# SmartDana.net
KiCad netlist of a schematic drawn in EAGLE
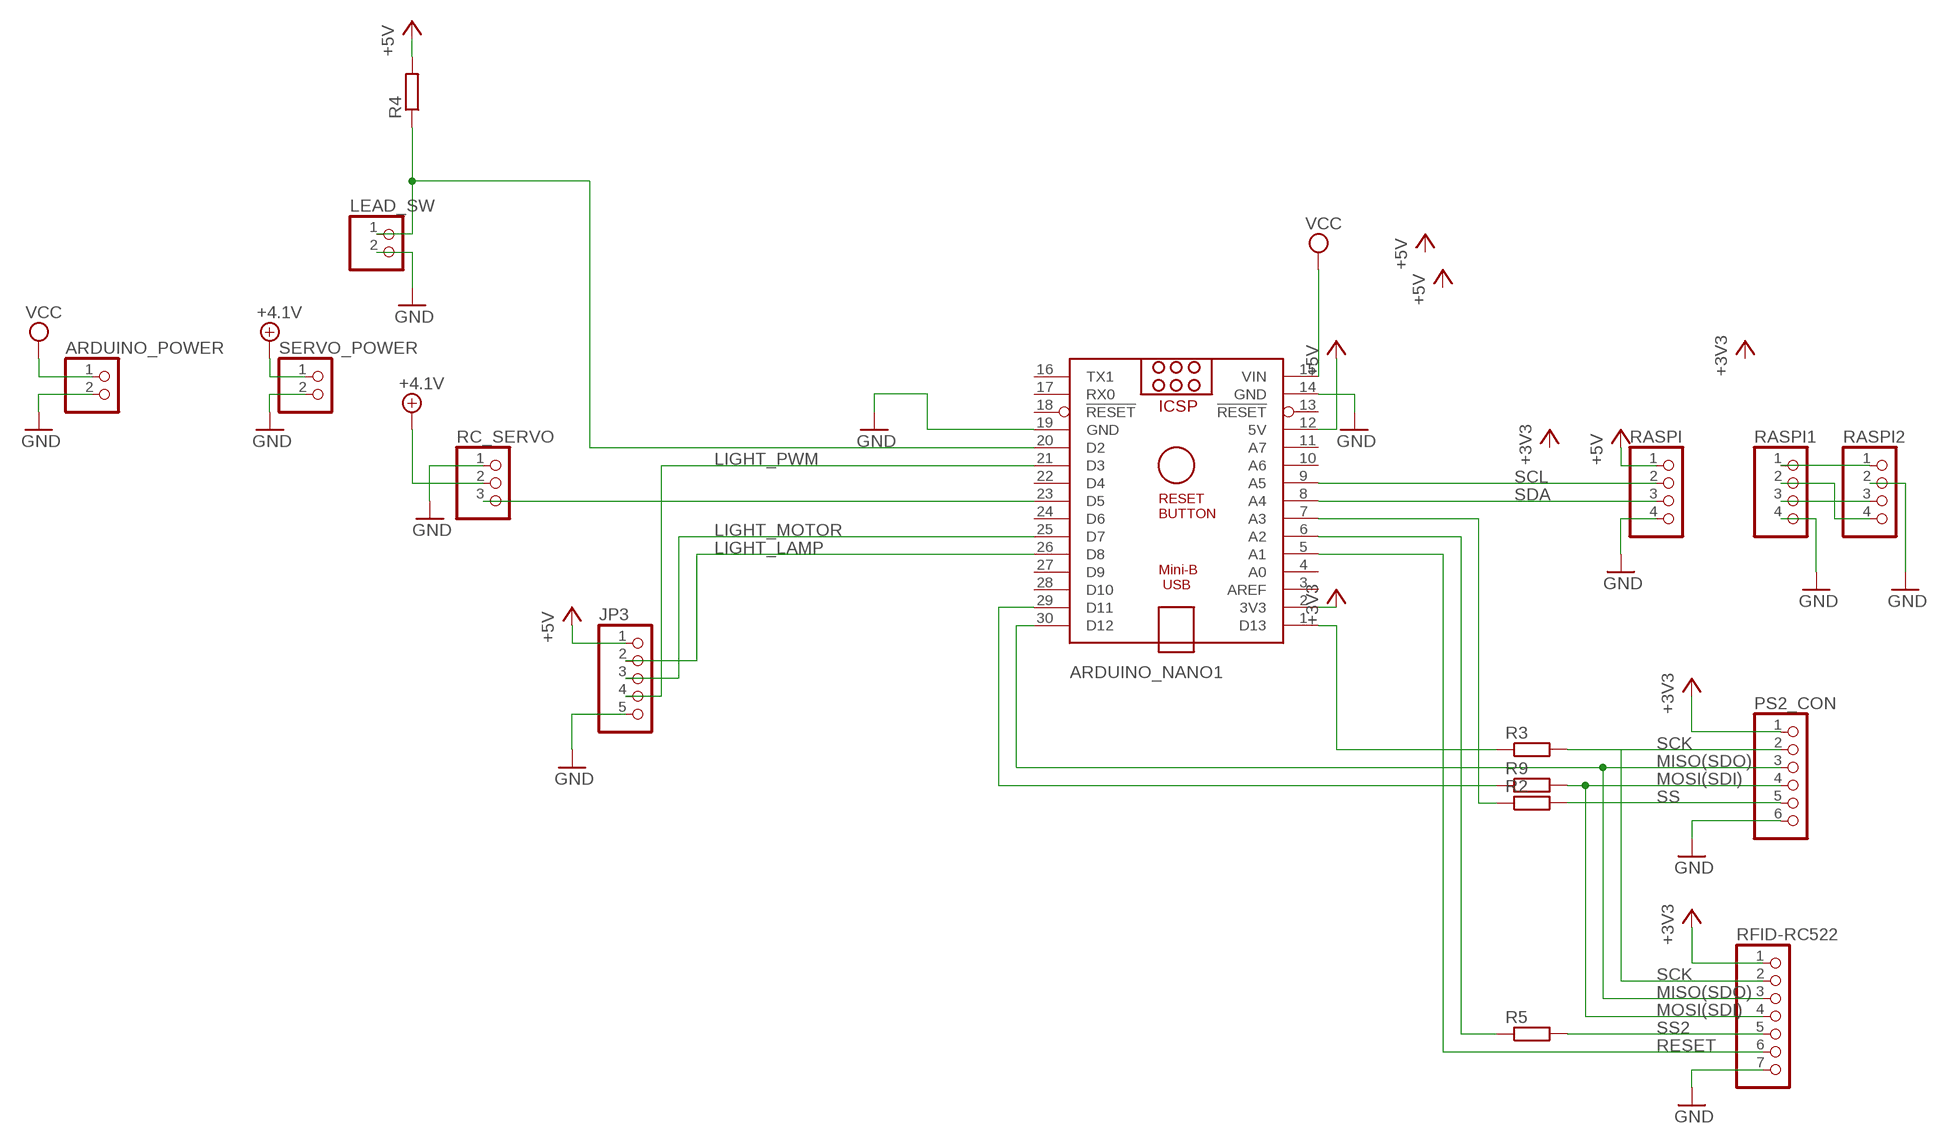
[diagram p0: schematic, sheet 1]

(export (version "E")
  (design (tool "Eeschema 10.0.6"))
  (components
    (comp (ref "ARDUINO_NANO1")
      (value "ARDUINO_NANO")
      (footprint "eagle-import:ARDUINO_NANO")
      (libsource (lib "eagle-import") (part "ARDUINO_NANO"))
    )
    (comp (ref "ARDUINO_POWER")
      (value "PINHD-1X2")
      (footprint "eagle-import:1X02")
      (libsource (lib "eagle-import") (part "PINHD-1X2"))
    )
    (comp (ref "JP3")
      (value "PINHD-1X5")
      (footprint "eagle-import:1X05")
      (libsource (lib "eagle-import") (part "PINHD-1X5"))
    )
    (comp (ref "LEAD_SW")
      (value "PINHD-1X2")
      (footprint "eagle-import:1X02")
      (libsource (lib "eagle-import") (part "PINHD-1X2"))
    )
    (comp (ref "PS2_CON")
      (value "PINHD-1X6")
      (footprint "eagle-import:1X06")
      (libsource (lib "eagle-import") (part "PINHD-1X6"))
    )
    (comp (ref "R2")
      (value "R-EU_0204/7")
      (footprint "eagle-import:0204_7")
      (libsource (lib "eagle-import") (part "R-EU_0204/7"))
    )
    (comp (ref "R3")
      (value "R-EU_0204/7")
      (footprint "eagle-import:0204_7")
      (libsource (lib "eagle-import") (part "R-EU_0204/7"))
    )
    (comp (ref "R4")
      (value "R-EU_0204/7")
      (footprint "eagle-import:0204_7")
      (libsource (lib "eagle-import") (part "R-EU_0204/7"))
    )
    (comp (ref "R5")
      (value "R-EU_0204/7")
      (footprint "eagle-import:0204_7")
      (libsource (lib "eagle-import") (part "R-EU_0204/7"))
    )
    (comp (ref "R9")
      (value "R-EU_0204/7")
      (footprint "eagle-import:0204_7")
      (libsource (lib "eagle-import") (part "R-EU_0204/7"))
    )
    (comp (ref "RASPI")
      (value "PINHD-1X4")
      (footprint "eagle-import:1X04")
      (libsource (lib "eagle-import") (part "PINHD-1X4"))
    )
    (comp (ref "RASPI1")
      (value "PINHD-1X4")
      (footprint "eagle-import:1X04")
      (libsource (lib "eagle-import") (part "PINHD-1X4"))
    )
    (comp (ref "RASPI2")
      (value "PINHD-1X4")
      (footprint "eagle-import:1X04")
      (libsource (lib "eagle-import") (part "PINHD-1X4"))
    )
    (comp (ref "RC_SERVO")
      (value "PINHD-1X3")
      (footprint "eagle-import:1X03")
      (libsource (lib "eagle-import") (part "PINHD-1X3"))
    )
    (comp (ref "RFID-RC522")
      (value "PINHD-1X7")
      (footprint "eagle-import:1X07")
      (libsource (lib "eagle-import") (part "PINHD-1X7"))
    )
    (comp (ref "SERVO_POWER")
      (value "PINHD-1X2")
      (footprint "eagle-import:1X02")
      (libsource (lib "eagle-import") (part "PINHD-1X2"))
    )
  )
  (nets
    (net (code "1") (name "+3V3") (class "Default")
      (node (ref "ARDUINO_NANO1") (pin "2") (pinfunction "3V3_2") (pintype "output"))
      (node (ref "PS2_CON") (pin "1") (pinfunction "1_1") (pintype "passive"))
      (node (ref "RFID-RC522") (pin "1") (pinfunction "1_1") (pintype "passive"))
    )
    (net (code "2") (name "+4.1V") (class "Default")
      (node (ref "RC_SERVO") (pin "2") (pinfunction "2_2") (pintype "passive"))
      (node (ref "SERVO_POWER") (pin "1") (pinfunction "1_1") (pintype "passive"))
    )
    (net (code "3") (name "+5V") (class "Default")
      (node (ref "ARDUINO_NANO1") (pin "12") (pinfunction "5V_12") (pintype "power_in"))
      (node (ref "JP3") (pin "1") (pinfunction "1_1") (pintype "passive"))
      (node (ref "R4") (pin "2") (pinfunction "2_2") (pintype "passive"))
      (node (ref "RASPI") (pin "1") (pinfunction "1_1") (pintype "passive"))
    )
    (net (code "4") (name "/LIGHT_LAMP") (class "Default")
      (node (ref "ARDUINO_NANO1") (pin "26") (pinfunction "D8_26") (pintype "bidirectional"))
      (node (ref "JP3") (pin "2") (pinfunction "2_2") (pintype "passive"))
    )
    (net (code "5") (name "/LIGHT_MOTOR") (class "Default")
      (node (ref "ARDUINO_NANO1") (pin "25") (pinfunction "D7_25") (pintype "bidirectional"))
      (node (ref "JP3") (pin "3") (pinfunction "3_3") (pintype "passive"))
    )
    (net (code "6") (name "/LIGHT_PWM") (class "Default")
      (node (ref "ARDUINO_NANO1") (pin "21") (pinfunction "D3_21") (pintype "bidirectional"))
      (node (ref "JP3") (pin "4") (pinfunction "4_4") (pintype "passive"))
    )
    (net (code "7") (name "/MISO(SDO)") (class "Default")
      (node (ref "ARDUINO_NANO1") (pin "30") (pinfunction "D12_30") (pintype "bidirectional"))
      (node (ref "PS2_CON") (pin "3") (pinfunction "3_3") (pintype "passive"))
      (node (ref "RFID-RC522") (pin "3") (pinfunction "3_3") (pintype "passive"))
    )
    (net (code "8") (name "/MOSI(SDI)") (class "Default")
      (node (ref "PS2_CON") (pin "4") (pinfunction "4_4") (pintype "passive"))
      (node (ref "R9") (pin "2") (pinfunction "2_2") (pintype "passive"))
      (node (ref "RFID-RC522") (pin "4") (pinfunction "4_4") (pintype "passive"))
    )
    (net (code "9") (name "/RESET") (class "Default")
      (node (ref "ARDUINO_NANO1") (pin "5") (pinfunction "A1_5") (pintype "bidirectional"))
      (node (ref "RFID-RC522") (pin "6") (pinfunction "6_6") (pintype "passive"))
    )
    (net (code "10") (name "/SCK") (class "Default")
      (node (ref "PS2_CON") (pin "2") (pinfunction "2_2") (pintype "passive"))
      (node (ref "R3") (pin "2") (pinfunction "2_2") (pintype "passive"))
      (node (ref "RFID-RC522") (pin "2") (pinfunction "2_2") (pintype "passive"))
    )
    (net (code "11") (name "/SCL") (class "Default")
      (node (ref "ARDUINO_NANO1") (pin "9") (pinfunction "A5_9") (pintype "bidirectional"))
      (node (ref "RASPI") (pin "2") (pinfunction "2_2") (pintype "passive"))
    )
    (net (code "12") (name "/SDA") (class "Default")
      (node (ref "ARDUINO_NANO1") (pin "8") (pinfunction "A4_8") (pintype "bidirectional"))
      (node (ref "RASPI") (pin "3") (pinfunction "3_3") (pintype "passive"))
    )
    (net (code "13") (name "/SS") (class "Default")
      (node (ref "PS2_CON") (pin "5") (pinfunction "5_5") (pintype "passive"))
      (node (ref "R2") (pin "2") (pinfunction "2_2") (pintype "passive"))
    )
    (net (code "14") (name "/SS2") (class "Default")
      (node (ref "R5") (pin "2") (pinfunction "2_2") (pintype "passive"))
      (node (ref "RFID-RC522") (pin "5") (pinfunction "5_5") (pintype "passive"))
    )
    (net (code "15") (name "GND") (class "Default")
      (node (ref "ARDUINO_NANO1") (pin "14") (pinfunction "GND_14") (pintype "power_in"))
      (node (ref "ARDUINO_NANO1") (pin "19") (pinfunction "GND_19") (pintype "power_in"))
      (node (ref "ARDUINO_POWER") (pin "2") (pinfunction "2_2") (pintype "passive"))
      (node (ref "JP3") (pin "5") (pinfunction "5_5") (pintype "passive"))
      (node (ref "LEAD_SW") (pin "2") (pinfunction "2_2") (pintype "passive"))
      (node (ref "PS2_CON") (pin "6") (pinfunction "6_6") (pintype "passive"))
      (node (ref "RASPI") (pin "4") (pinfunction "4_4") (pintype "passive"))
      (node (ref "RASPI1") (pin "4") (pinfunction "4_4") (pintype "passive"))
      (node (ref "RASPI2") (pin "2") (pinfunction "2_2") (pintype "passive"))
      (node (ref "RC_SERVO") (pin "1") (pinfunction "1_1") (pintype "passive"))
      (node (ref "RFID-RC522") (pin "7") (pinfunction "7_7") (pintype "passive"))
      (node (ref "SERVO_POWER") (pin "2") (pinfunction "2_2") (pintype "passive"))
    )
    (net (code "16") (name "Net-(ARDUINO_NANO1-A2)") (class "Default")
      (node (ref "ARDUINO_NANO1") (pin "6") (pinfunction "A2_6") (pintype "bidirectional"))
      (node (ref "R5") (pin "1") (pinfunction "1_1") (pintype "passive"))
    )
    (net (code "17") (name "Net-(ARDUINO_NANO1-A3)") (class "Default")
      (node (ref "ARDUINO_NANO1") (pin "7") (pinfunction "A3_7") (pintype "bidirectional"))
      (node (ref "R2") (pin "1") (pinfunction "1_1") (pintype "passive"))
    )
    (net (code "18") (name "Net-(ARDUINO_NANO1-D2)") (class "Default")
      (node (ref "ARDUINO_NANO1") (pin "20") (pinfunction "D2_20") (pintype "bidirectional"))
      (node (ref "LEAD_SW") (pin "1") (pinfunction "1_1") (pintype "passive"))
      (node (ref "R4") (pin "1") (pinfunction "1_1") (pintype "passive"))
    )
    (net (code "19") (name "Net-(ARDUINO_NANO1-D5)") (class "Default")
      (node (ref "ARDUINO_NANO1") (pin "23") (pinfunction "D5_23") (pintype "bidirectional"))
      (node (ref "RC_SERVO") (pin "3") (pinfunction "3_3") (pintype "passive"))
    )
    (net (code "20") (name "Net-(ARDUINO_NANO1-D11)") (class "Default")
      (node (ref "ARDUINO_NANO1") (pin "29") (pinfunction "D11_29") (pintype "bidirectional"))
      (node (ref "R9") (pin "1") (pinfunction "1_1") (pintype "passive"))
    )
    (net (code "21") (name "Net-(ARDUINO_NANO1-D13)") (class "Default")
      (node (ref "ARDUINO_NANO1") (pin "1") (pinfunction "D13_1") (pintype "bidirectional"))
      (node (ref "R3") (pin "1") (pinfunction "1_1") (pintype "passive"))
    )
    (net (code "22") (name "Net-(RASPI1-Pad1)") (class "Default")
      (node (ref "RASPI1") (pin "1") (pinfunction "1_1") (pintype "passive"))
      (node (ref "RASPI2") (pin "1") (pinfunction "1_1") (pintype "passive"))
    )
    (net (code "23") (name "Net-(RASPI1-Pad2)") (class "Default")
      (node (ref "RASPI1") (pin "2") (pinfunction "2_2") (pintype "passive"))
      (node (ref "RASPI2") (pin "4") (pinfunction "4_4") (pintype "passive"))
    )
    (net (code "24") (name "Net-(RASPI1-Pad3)") (class "Default")
      (node (ref "RASPI1") (pin "3") (pinfunction "3_3") (pintype "passive"))
      (node (ref "RASPI2") (pin "3") (pinfunction "3_3") (pintype "passive"))
    )
    (net (code "25") (name "VCC") (class "Default")
      (node (ref "ARDUINO_NANO1") (pin "15") (pinfunction "VIN_15") (pintype "power_in"))
      (node (ref "ARDUINO_POWER") (pin "1") (pinfunction "1_1") (pintype "passive"))
    )
    (net (code "26") (name "unconnected-(ARDUINO_NANO1-A0-Pad4)") (class "Default")
      (node (ref "ARDUINO_NANO1") (pin "4") (pinfunction "A0_4") (pintype "bidirectional"))
    )
    (net (code "27") (name "unconnected-(ARDUINO_NANO1-A6-Pad10)") (class "Default")
      (node (ref "ARDUINO_NANO1") (pin "10") (pinfunction "A6_10") (pintype "bidirectional"))
    )
    (net (code "28") (name "unconnected-(ARDUINO_NANO1-A7-Pad11)") (class "Default")
      (node (ref "ARDUINO_NANO1") (pin "11") (pinfunction "A7_11") (pintype "bidirectional"))
    )
    (net (code "29") (name "unconnected-(ARDUINO_NANO1-AREF-Pad3)") (class "Default")
      (node (ref "ARDUINO_NANO1") (pin "3") (pinfunction "AREF_3") (pintype "input"))
    )
    (net (code "30") (name "unconnected-(ARDUINO_NANO1-D4-Pad22)") (class "Default")
      (node (ref "ARDUINO_NANO1") (pin "22") (pinfunction "D4_22") (pintype "bidirectional"))
    )
    (net (code "31") (name "unconnected-(ARDUINO_NANO1-D6-Pad24)") (class "Default")
      (node (ref "ARDUINO_NANO1") (pin "24") (pinfunction "D6_24") (pintype "bidirectional"))
    )
    (net (code "32") (name "unconnected-(ARDUINO_NANO1-D9-Pad27)") (class "Default")
      (node (ref "ARDUINO_NANO1") (pin "27") (pinfunction "D9_27") (pintype "bidirectional"))
    )
    (net (code "33") (name "unconnected-(ARDUINO_NANO1-D10-Pad28)") (class "Default")
      (node (ref "ARDUINO_NANO1") (pin "28") (pinfunction "D10_28") (pintype "bidirectional"))
    )
    (net (code "34") (name "unconnected-(ARDUINO_NANO1-RX0-Pad17)") (class "Default")
      (node (ref "ARDUINO_NANO1") (pin "17") (pinfunction "RX0_17") (pintype "bidirectional"))
    )
    (net (code "35") (name "unconnected-(ARDUINO_NANO1-TX1-Pad16)") (class "Default")
      (node (ref "ARDUINO_NANO1") (pin "16") (pinfunction "TX1_16") (pintype "bidirectional"))
    )
    (net (code "36") (name "unconnected-(ARDUINO_NANO1-~{RESET}-Pad13)") (class "Default")
      (node (ref "ARDUINO_NANO1") (pin "13") (pinfunction "~{RESET}_13") (pintype "input"))
    )
    (net (code "37") (name "unconnected-(ARDUINO_NANO1-~{RESET}-Pad18)") (class "Default")
      (node (ref "ARDUINO_NANO1") (pin "18") (pinfunction "~{RESET}_18") (pintype "input"))
    )
  )
)
